# IO_Expander.net
KiCad netlist of a schematic drawn in Altium Designer
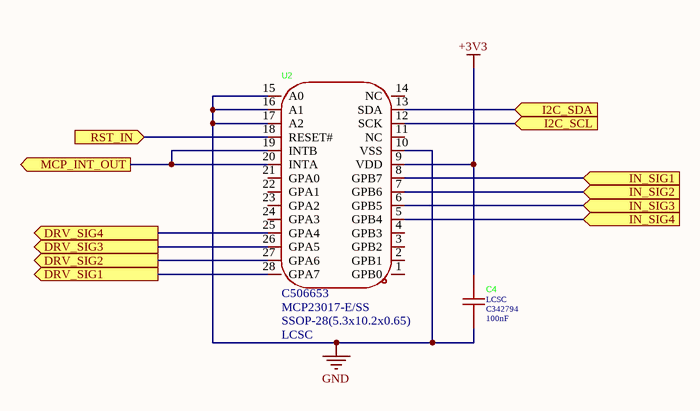
[diagram p0: IO_Expander.SchDoc]

(export (version "E")
  (design (tool "Eeschema 10.0.6"))
  (components
    (comp (ref "C4")
      (value "100nF")
      (footprint "CAP-TH_L4.0-W2.5-P5.00-D1.0:CAP-TH_L4.0-W2.5-P5.00-D1.0")
      (fields
        (field (name "MANUFACTURER") "TDK")
        (field (name "MANUFACTURER PART") "FG28X7R1H104KNT06")
        (field (name "TOLERANCE") "±10%")
        (field (name "SUPPLIER") "LCSC")
        (field (name "SUPPLIER PART") "C342794")
      )
      (libsource (lib "FG28X7R1H104KNT061_FG28X7R1H104KNT06") (part "FG28X7R1H104KNT06"))
    )
    (comp (ref "U2")
      (value "MCP23017-E/SS")
      (footprint "SSOP-28_L10.2-W5.3-P0.65-LS7.8-BL")
      (fields
        (field (name "MANUFACTURER") "MICROCHIP(美国微芯)")
        (field (name "SUPPLIER PART") "C506653")
        (field (name "MANUFACTURER PART") "MCP23017-E/SS")
        (field (name "SUPPLIER FOOTPRINT") "SSOP-28(5.3x10.2x0.65)")
        (field (name "SUPPLIER") "LCSC")
      )
      (libsource (lib "MCP23017-E-SS") (part "MCP23017-E/SS"))
    )
  )
  (nets
    (net (code "1") (name "+3V3") (class "Default")
      (node (ref "C4") (pin "2") (pinfunction "2_2") (pintype "passive"))
      (node (ref "U2") (pin "9") (pinfunction "VDD_9") (pintype "passive"))
    )
    (net (code "2") (name "/DRV_SIG1") (class "Default")
      (node (ref "U2") (pin "28") (pinfunction "GPA7_28") (pintype "passive"))
    )
    (net (code "3") (name "/DRV_SIG2") (class "Default")
      (node (ref "U2") (pin "27") (pinfunction "GPA6_27") (pintype "passive"))
    )
    (net (code "4") (name "/DRV_SIG3") (class "Default")
      (node (ref "U2") (pin "26") (pinfunction "GPA5_26") (pintype "passive"))
    )
    (net (code "5") (name "/DRV_SIG4") (class "Default")
      (node (ref "U2") (pin "25") (pinfunction "GPA4_25") (pintype "passive"))
    )
    (net (code "6") (name "/I2C_SCL") (class "Default")
      (node (ref "U2") (pin "12") (pinfunction "SCK_12") (pintype "passive"))
    )
    (net (code "7") (name "/I2C_SDA") (class "Default")
      (node (ref "U2") (pin "13") (pinfunction "SDA_13") (pintype "passive"))
    )
    (net (code "8") (name "/IN_SIG1") (class "Default")
      (node (ref "U2") (pin "8") (pinfunction "GPB7_8") (pintype "passive"))
    )
    (net (code "9") (name "/IN_SIG2") (class "Default")
      (node (ref "U2") (pin "7") (pinfunction "GPB6_7") (pintype "passive"))
    )
    (net (code "10") (name "/IN_SIG3") (class "Default")
      (node (ref "U2") (pin "6") (pinfunction "GPB5_6") (pintype "passive"))
    )
    (net (code "11") (name "/IN_SIG4") (class "Default")
      (node (ref "U2") (pin "5") (pinfunction "GPB4_5") (pintype "passive"))
    )
    (net (code "12") (name "/MCP_INT_OUT") (class "Default")
      (node (ref "U2") (pin "19") (pinfunction "INTB_19") (pintype "passive"))
      (node (ref "U2") (pin "20") (pinfunction "INTA_20") (pintype "passive"))
    )
    (net (code "13") (name "/RST_IN") (class "Default")
      (node (ref "U2") (pin "18") (pinfunction "RESET#_18") (pintype "passive"))
    )
    (net (code "14") (name "GND") (class "Default")
      (node (ref "C4") (pin "1") (pinfunction "1_1") (pintype "passive"))
      (node (ref "U2") (pin "10") (pinfunction "VSS_10") (pintype "passive"))
      (node (ref "U2") (pin "15") (pinfunction "A0_15") (pintype "passive"))
      (node (ref "U2") (pin "16") (pinfunction "A1_16") (pintype "passive"))
      (node (ref "U2") (pin "17") (pinfunction "A2_17") (pintype "passive"))
    )
    (net (code "15") (name "unconnected-(U2-GPA0-Pad21)") (class "Default")
      (node (ref "U2") (pin "21") (pinfunction "GPA0_21") (pintype "passive"))
    )
    (net (code "16") (name "unconnected-(U2-GPA1-Pad22)") (class "Default")
      (node (ref "U2") (pin "22") (pinfunction "GPA1_22") (pintype "passive"))
    )
    (net (code "17") (name "unconnected-(U2-GPA2-Pad23)") (class "Default")
      (node (ref "U2") (pin "23") (pinfunction "GPA2_23") (pintype "passive"))
    )
    (net (code "18") (name "unconnected-(U2-GPA3-Pad24)") (class "Default")
      (node (ref "U2") (pin "24") (pinfunction "GPA3_24") (pintype "passive"))
    )
    (net (code "19") (name "unconnected-(U2-GPB0-Pad1)") (class "Default")
      (node (ref "U2") (pin "1") (pinfunction "GPB0_1") (pintype "passive"))
    )
    (net (code "20") (name "unconnected-(U2-GPB1-Pad2)") (class "Default")
      (node (ref "U2") (pin "2") (pinfunction "GPB1_2") (pintype "passive"))
    )
    (net (code "21") (name "unconnected-(U2-GPB2-Pad3)") (class "Default")
      (node (ref "U2") (pin "3") (pinfunction "GPB2_3") (pintype "passive"))
    )
    (net (code "22") (name "unconnected-(U2-GPB3-Pad4)") (class "Default")
      (node (ref "U2") (pin "4") (pinfunction "GPB3_4") (pintype "passive"))
    )
    (net (code "23") (name "unconnected-(U2-NC-Pad11)") (class "Default")
      (node (ref "U2") (pin "11") (pinfunction "NC_11") (pintype "passive"))
    )
    (net (code "24") (name "unconnected-(U2-NC-Pad14)") (class "Default")
      (node (ref "U2") (pin "14") (pinfunction "NC_14") (pintype "passive"))
    )
  )
)
